# MCU023_XDS110_Target_Interface.net
KiCad netlist of a schematic drawn in Altium Designer
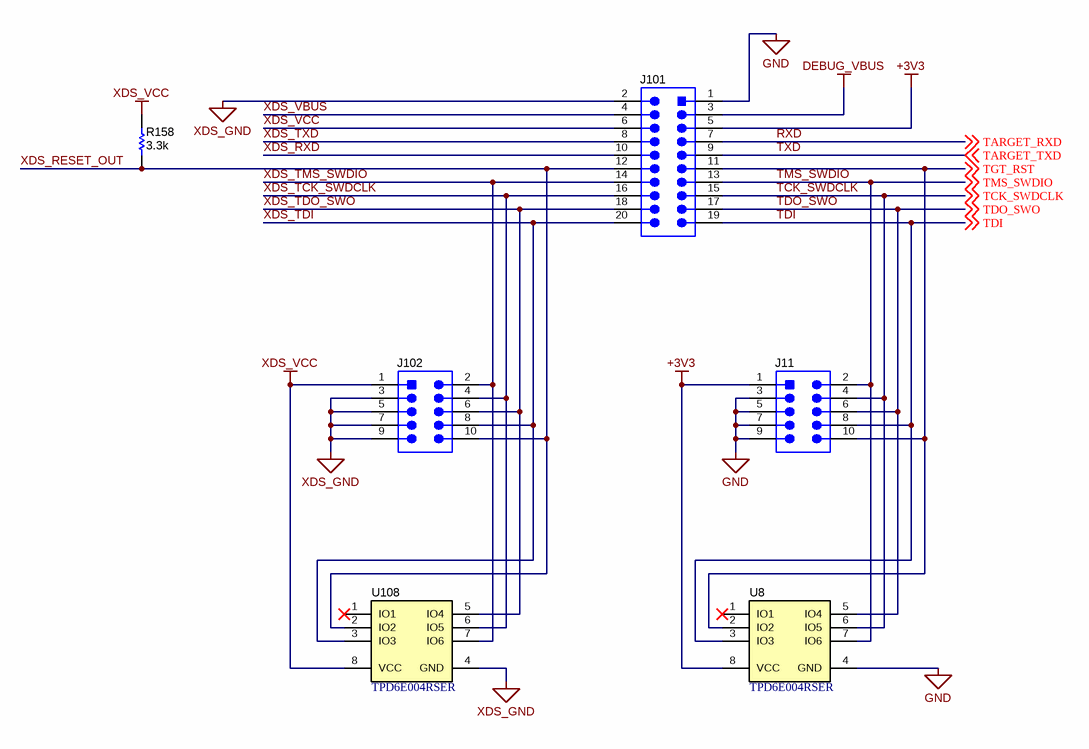
[diagram p0: MCU023_XDS110_Target_Interface.SchDoc]

(export (version "E")
  (design (tool "Eeschema 10.0.6"))
  (components
    (comp (ref "J11")
      (value "FTSH-105-01-F-DV-K")
      (footprint "Samtec_FTSH-105-01-x-DV-K")
      (description "Header (Shrouded), 1.27mm, 5x2, Gold, SMT")
      (fields
        (field (name "MANUFACTURER") "Samtec")
        (field (name "SYMBOLCREATOR") "a0412235")
        (field (name "PUBLISHER") "Texas Instruments")
      )
      (libsource (lib "Connectors_Samtec") (part "FTSH-105-01-F-DV-K"))
    )
    (comp (ref "J101")
      (value "PEC10DAAN")
      (footprint "SULLINS_PEC10DAAN")
      (description "Header, 2.54mm, 10x2, Tin, TH")
      (fields
        (field (name "MANUFACTURER") "Sullins Connector Solutions")
        (field (name "SYMBOLCREATOR") "a0412235")
        (field (name "PUBLISHER") "Texas Instruments")
      )
      (libsource (lib "Connectors_Sullins") (part "PEC10DAAN"))
    )
    (comp (ref "J102")
      (value "FTSH-105-01-F-DV-K")
      (footprint "Samtec_FTSH-105-01-x-DV-K")
      (description "Header (Shrouded), 1.27mm, 5x2, Gold, SMT")
      (fields
        (field (name "MANUFACTURER") "Samtec")
        (field (name "SYMBOLCREATOR") "a0412235")
        (field (name "PUBLISHER") "Texas Instruments")
      )
      (libsource (lib "Connectors_Samtec") (part "FTSH-105-01-F-DV-K"))
    )
    (comp (ref "R158")
      (value "CRCW04023K30JNED")
      (footprint "0402")
      (description "RES, 3.3 k, 5%, 0.063 W, 0402")
      (fields
        (field (name "VALUEDISPLAYED") "3.3k")
        (field (name "MANUFACTURER") "Vishay-Dale")
        (field (name "PUBLISHER") "Texas Instruments")
      )
      (libsource (lib "Resistor_0402") (part "CRCW04023K30JNED"))
    )
    (comp (ref "U8")
      (value "TPD6E004RSER")
      (footprint "RSE0008A")
      (fields
        (field (name "MANUFACTURER") "Texas Instruments")
        (field (name "ALTERNATE PARTNUMBER") "Equivalent")
      )
      (libsource (lib "TI Interface ESD EMI Protection") (part "TPD6E004RSER"))
    )
    (comp (ref "U108")
      (value "TPD6E004RSER")
      (footprint "RSE0008A")
      (fields
        (field (name "MANUFACTURER") "Texas Instruments")
        (field (name "ALTERNATE PARTNUMBER") "Equivalent")
      )
      (libsource (lib "TI Interface ESD EMI Protection") (part "TPD6E004RSER"))
    )
  )
  (nets
    (net (code "1") (name "+3V3") (class "Default")
      (node (ref "J101") (pin "5") (pinfunction "5_5") (pintype "passive"))
      (node (ref "J11") (pin "1") (pinfunction "1_1") (pintype "passive"))
      (node (ref "U8") (pin "8") (pinfunction "VCC_8") (pintype "power_in"))
    )
    (net (code "2") (name "/XDS_RESET_OUT") (class "Default")
      (node (ref "J101") (pin "12") (pinfunction "12_12") (pintype "passive"))
      (node (ref "J102") (pin "10") (pinfunction "10_10") (pintype "passive"))
      (node (ref "R158") (pin "1") (pinfunction "1_1") (pintype "passive"))
      (node (ref "U108") (pin "2") (pinfunction "IO2_2") (pintype "passive"))
    )
    (net (code "3") (name "/XDS_RXD") (class "Default")
      (node (ref "J101") (pin "10") (pinfunction "10_10") (pintype "passive"))
    )
    (net (code "4") (name "/XDS_TCK_SWDCLK") (class "Default")
      (node (ref "J101") (pin "16") (pinfunction "16_16") (pintype "passive"))
      (node (ref "J102") (pin "4") (pinfunction "4_4") (pintype "passive"))
      (node (ref "U108") (pin "6") (pinfunction "IO5_6") (pintype "passive"))
    )
    (net (code "5") (name "/XDS_TDI") (class "Default")
      (node (ref "J101") (pin "20") (pinfunction "20_20") (pintype "passive"))
      (node (ref "J102") (pin "8") (pinfunction "8_8") (pintype "passive"))
      (node (ref "U108") (pin "3") (pinfunction "IO3_3") (pintype "passive"))
    )
    (net (code "6") (name "/XDS_TDO_SWO") (class "Default")
      (node (ref "J101") (pin "18") (pinfunction "18_18") (pintype "passive"))
      (node (ref "J102") (pin "6") (pinfunction "6_6") (pintype "passive"))
      (node (ref "U108") (pin "5") (pinfunction "IO4_5") (pintype "passive"))
    )
    (net (code "7") (name "/XDS_TMS_SWDIO") (class "Default")
      (node (ref "J101") (pin "14") (pinfunction "14_14") (pintype "passive"))
      (node (ref "J102") (pin "2") (pinfunction "2_2") (pintype "passive"))
      (node (ref "U108") (pin "7") (pinfunction "IO6_7") (pintype "passive"))
    )
    (net (code "8") (name "/XDS_TXD") (class "Default")
      (node (ref "J101") (pin "8") (pinfunction "8_8") (pintype "passive"))
    )
    (net (code "9") (name "/XDS_VBUS") (class "Default")
      (node (ref "J101") (pin "4") (pinfunction "4_4") (pintype "passive"))
    )
    (net (code "10") (name "DEBUG_VBUS") (class "Default")
      (node (ref "J101") (pin "3") (pinfunction "3_3") (pintype "passive"))
    )
    (net (code "11") (name "GND") (class "Default")
      (node (ref "J101") (pin "1") (pinfunction "1_1") (pintype "passive"))
      (node (ref "J11") (pin "3") (pinfunction "3_3") (pintype "passive"))
      (node (ref "J11") (pin "5") (pinfunction "5_5") (pintype "passive"))
      (node (ref "J11") (pin "7") (pinfunction "7_7") (pintype "passive"))
      (node (ref "J11") (pin "9") (pinfunction "9_9") (pintype "passive"))
      (node (ref "U8") (pin "4") (pinfunction "GND_4") (pintype "power_in"))
    )
    (net (code "12") (name "TARGET_RXD") (class "Default")
      (node (ref "J101") (pin "7") (pinfunction "7_7") (pintype "passive"))
    )
    (net (code "13") (name "TARGET_TXD") (class "Default")
      (node (ref "J101") (pin "9") (pinfunction "9_9") (pintype "passive"))
    )
    (net (code "14") (name "TCK_SWDCLK") (class "Default")
      (node (ref "J101") (pin "15") (pinfunction "15_15") (pintype "passive"))
      (node (ref "J11") (pin "4") (pinfunction "4_4") (pintype "passive"))
      (node (ref "U8") (pin "6") (pinfunction "IO5_6") (pintype "passive"))
    )
    (net (code "15") (name "TDI") (class "Default")
      (node (ref "J101") (pin "19") (pinfunction "19_19") (pintype "passive"))
      (node (ref "J11") (pin "8") (pinfunction "8_8") (pintype "passive"))
      (node (ref "U8") (pin "3") (pinfunction "IO3_3") (pintype "passive"))
    )
    (net (code "16") (name "TDO_SWO") (class "Default")
      (node (ref "J101") (pin "17") (pinfunction "17_17") (pintype "passive"))
      (node (ref "J11") (pin "6") (pinfunction "6_6") (pintype "passive"))
      (node (ref "U8") (pin "5") (pinfunction "IO4_5") (pintype "passive"))
    )
    (net (code "17") (name "TGT_RST") (class "Default")
      (node (ref "J101") (pin "11") (pinfunction "11_11") (pintype "passive"))
      (node (ref "J11") (pin "10") (pinfunction "10_10") (pintype "passive"))
      (node (ref "U8") (pin "2") (pinfunction "IO2_2") (pintype "passive"))
    )
    (net (code "18") (name "TMS_SWDIO") (class "Default")
      (node (ref "J101") (pin "13") (pinfunction "13_13") (pintype "passive"))
      (node (ref "J11") (pin "2") (pinfunction "2_2") (pintype "passive"))
      (node (ref "U8") (pin "7") (pinfunction "IO6_7") (pintype "passive"))
    )
    (net (code "19") (name "XDS_GND") (class "Default")
      (node (ref "J101") (pin "2") (pinfunction "2_2") (pintype "passive"))
      (node (ref "J102") (pin "3") (pinfunction "3_3") (pintype "passive"))
      (node (ref "J102") (pin "5") (pinfunction "5_5") (pintype "passive"))
      (node (ref "J102") (pin "7") (pinfunction "7_7") (pintype "passive"))
      (node (ref "J102") (pin "9") (pinfunction "9_9") (pintype "passive"))
      (node (ref "U108") (pin "4") (pinfunction "GND_4") (pintype "power_in"))
    )
    (net (code "20") (name "XDS_VCC") (class "Default")
      (node (ref "J101") (pin "6") (pinfunction "6_6") (pintype "passive"))
      (node (ref "J102") (pin "1") (pinfunction "1_1") (pintype "passive"))
      (node (ref "R158") (pin "2") (pinfunction "2_2") (pintype "passive"))
      (node (ref "U108") (pin "8") (pinfunction "VCC_8") (pintype "power_in"))
    )
    (net (code "21") (name "unconnected-(U8-IO1-Pad1)") (class "Default")
      (node (ref "U8") (pin "1") (pinfunction "IO1_1") (pintype "passive+no_connect"))
    )
    (net (code "22") (name "unconnected-(U108-IO1-Pad1)") (class "Default")
      (node (ref "U108") (pin "1") (pinfunction "IO1_1") (pintype "passive+no_connect"))
    )
  )
)
